# 5VPrimary.net
KiCad netlist of a schematic drawn in Altium Designer
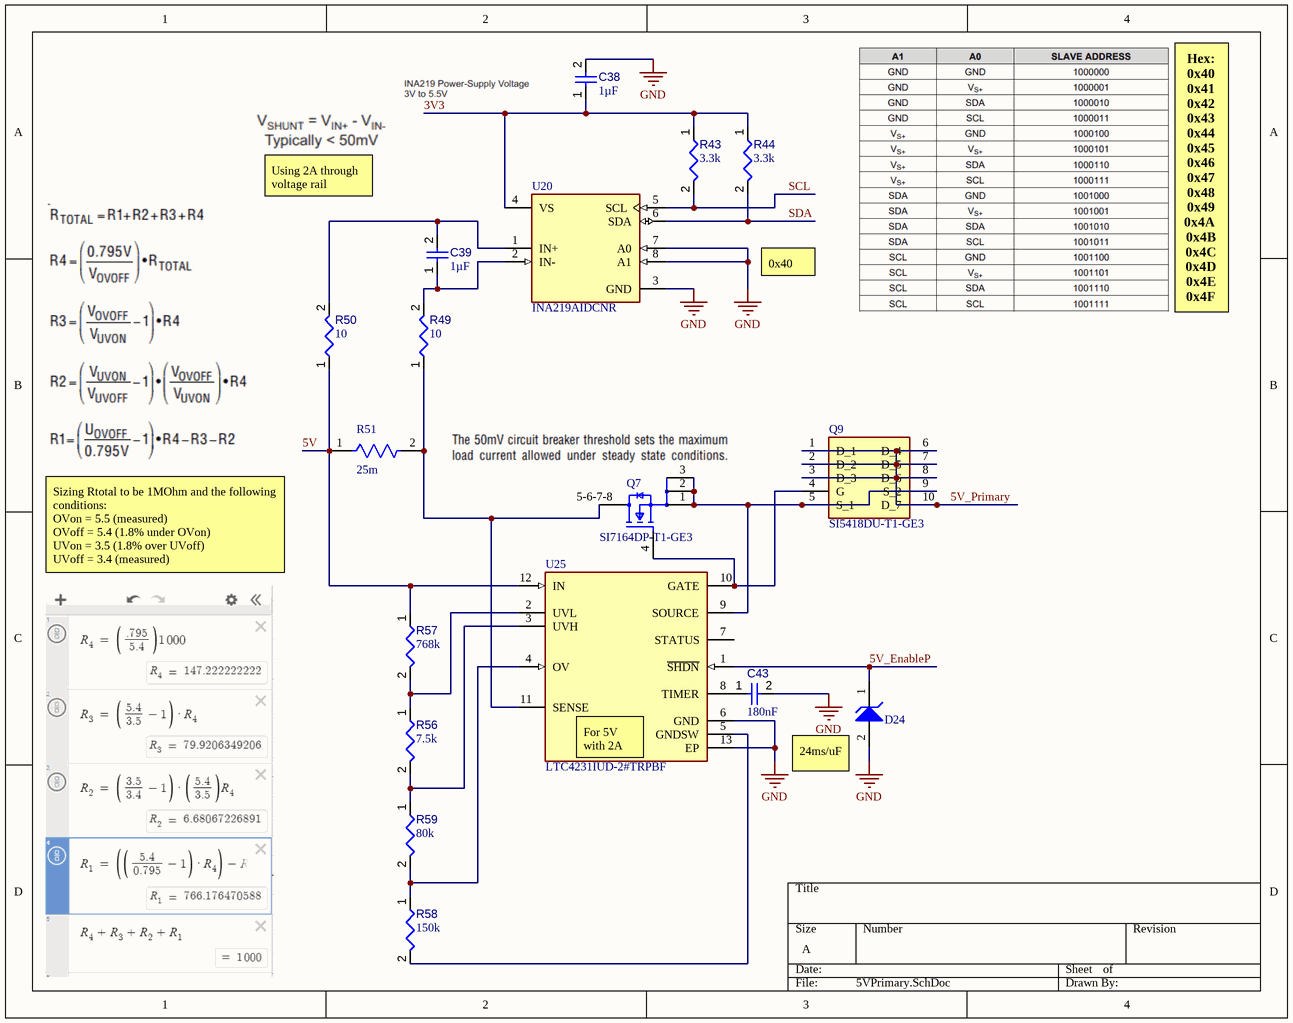
[diagram p0: 5VPrimary.SchDoc]

(export (version "E")
  (design (tool "Eeschema 10.0.6"))
  (components
    (comp (ref "C38")
      (value "1µF")
      (footprint "CAPC1608X90X35ML15T15")
      (description "Chip Capacitor, 1 uF, +/- 10%, 16 V, 0603 (1608 Metric)")
      (fields (field (name "TOLERANCE") "10%") (field (name "Comment") "Capacitor 1uF +/- 10% 16V 0603"))
      (libsource (lib "UGA SSRL Hardware Team") (part "CAP-NP-2"))
    )
    (comp (ref "C39")
      (value "1µF")
      (footprint "CAPC1608X90X40LL10T20")
      (description "Chip Capacitor, 1 uF, +/- 10%, 25 V, 0603 (1608 Metric)")
      (fields (field (name "TOLERANCE") "10%") (field (name "Comment") "Capacitor 1 uF +/- 10% 25 V 0603"))
      (libsource (lib "UGA SSRL Hardware Team") (part "CAP-NP-2"))
    )
    (comp (ref "C43")
      (value "180nF")
      (footprint "FP-C0805C-DN-IPC_A")
      (fields (field (name "Comment") "C0805C184K5RACTU"))
      (libsource (lib "UGA SSRL Hardware Team") (part "CAP-NP-2"))
    )
    (comp (ref "D24")
      (value "MM3Z3V6T1G")
      (footprint "ONSC-SOD-323-2-477-02_V")
      (description "Zener Voltage Regulator, 300 mW, 2-Pin SOD-323, Pb-Free, Tape and Reel")
      (fields (field (name "MANUFACTURER") "On Semiconductor"))
      (libsource (lib "Altium Content Vault") (part "ONSC-K1A2-2"))
    )
    (comp (ref "Q7")
      (value "SI7164DP-T1-GE3")
      (footprint "Vishay_S17-0173-SINGLE_MFG")
      (libsource (lib "UGA SSRL Hardware Team") (part "SI7164DP-T1-GE3"))
    )
    (comp (ref "Q9")
      (value "SI5418DU-T1-GE3")
      (footprint "SI5418DU-T1-GE3-Footprint-1")
      (libsource (lib "UGA SSRL Hardware Team") (part "SI5418DU-T1-GE3-Symbol-1"))
    )
    (comp (ref "R43")
      (value "3.3k")
      (footprint "FP-CRCW1210-e3-IPC_C")
      (fields
        (field (name "TOLERANCE") "5%")
        (field (name "POWER") "500mW")
        (field (name "Comment") "CRCW12103K30JNEA")
      )
      (libsource (lib "UGA SSRL Hardware Team") (part "RES-2"))
    )
    (comp (ref "R44")
      (value "3.3k")
      (footprint "FP-CRCW1210-e3-IPC_C")
      (fields
        (field (name "TOLERANCE") "5%")
        (field (name "POWER") "500mW")
        (field (name "Comment") "CRCW12103K30JNEA")
      )
      (libsource (lib "UGA SSRL Hardware Team") (part "RES-2"))
    )
    (comp (ref "R49")
      (value "10")
      (footprint "RESC0402(1005)_L")
      (description "Chip Resistor, 10 Ohms, +/-1 %, 63 mW, -55 to 155 degC, 0402")
      (fields (field (name "TOLERANCE") "1%") (field (name "POWER") "63mW"))
      (libsource (lib "UGA SSRL Hardware Team") (part "RES-2"))
    )
    (comp (ref "R50")
      (value "10")
      (footprint "RESC0402(1005)_L")
      (description "Chip Resistor, 10 Ohms, +/-1 %, 63 mW, -55 to 155 degC, 0402")
      (fields (field (name "TOLERANCE") "1%") (field (name "POWER") "63mW"))
      (libsource (lib "UGA SSRL Hardware Team") (part "RES-2"))
    )
    (comp (ref "R51")
      (value "CSR1206FK25L0")
      (footprint "FP-CSR1206-IPC_C")
      (description "General Purpose Thick Film Chip Resistor, 1206, 25mΩ, 1%, 0.5W")
      (fields (field (name "RESISTANCE") "25m") (field (name "TOLERANCE") "1%"))
      (libsource (lib "Altium Content Vault") (part "1029c3af85768c4190bb7ad29bc67b5"))
    )
    (comp (ref "R56")
      (value "7.5k")
      (footprint "FP-CRCW1206-e3-IPC_A")
      (fields
        (field (name "TOLERANCE") "1%")
        (field (name "POWER") "250mW")
        (field (name "Comment") "CRCW12067K50FKEA")
      )
      (libsource (lib "UGA SSRL Hardware Team") (part "RES-2"))
    )
    (comp (ref "R57")
      (value "768k")
      (footprint "RESC0402(1005)_L")
      (description "768K 0.063W 1% 0402 (1005 Metric)  SMD")
      (fields (field (name "TOLERANCE") "1%") (field (name "POWER") "63mW"))
      (libsource (lib "UGA SSRL Hardware Team") (part "768KR2F"))
    )
    (comp (ref "R58")
      (value "150k")
      (footprint "FP-RT1206-IPC_C")
      (description "Fixed Resistor, Thin Film, 0.25W, 150000ohm, 200V, 1% +/-Tol, 50ppm/Cel, Surface Mount, 1206")
      (fields (field (name "TOLERANCE") "1%") (field (name "POWER") "250mW"))
      (libsource (lib "UGA SSRL Hardware Team") (part "RES-2"))
    )
    (comp (ref "R59")
      (value "80k")
      (footprint "FP-PTN0603-IPC_B")
      (description "Fixed Resistor, Thin Film, 0.15W, 80000ohm, 75V, 0.1% +/-Tol, 25ppm/Cel, Surface Mount, 0603")
      (fields (field (name "POWER") "150mW") (field (name "TOLERANCE") "0.1%"))
      (libsource (lib "UGA SSRL Hardware Team") (part "RES-2"))
    )
    (comp (ref "U20")
      (value "INA219AIDCNR")
      (footprint "FP-DCN0008A-IPC_A")
      (description "Power Supply Support Circuit, Fixed, 2 Channel, 2V, PDSO8")
      (libsource (lib "UGA SSRL Hardware Team") (part "e16934b8ef90d0e345b266f0ae9cd81"))
    )
    (comp (ref "U25")
      (value "LTC4231IUD-2#TRPBF")
      (footprint "FP-UD-12-05-08-1855-IPC_A")
      (description "Switching Controller, CMOS, PQCC12")
      (libsource (lib "UGA SSRL Hardware Team") (part "94c330ae140e2337d879337fe7aaeec"))
    )
  )
  (nets
    (net (code "1") (name "/3V3") (class "Default")
      (node (ref "C38") (pin "1") (pinfunction "1_1") (pintype "passive"))
      (node (ref "R43") (pin "1") (pinfunction "1_1") (pintype "passive"))
      (node (ref "R44") (pin "1") (pinfunction "1_1") (pintype "passive"))
      (node (ref "U20") (pin "4") (pinfunction "VS_4") (pintype "power_in"))
    )
    (net (code "2") (name "/5V") (class "Default")
      (node (ref "R50") (pin "1") (pinfunction "1_1") (pintype "passive"))
      (node (ref "R51") (pin "1") (pinfunction "1_1") (pintype "passive"))
      (node (ref "R57") (pin "1") (pinfunction "1_1") (pintype "passive"))
      (node (ref "U25") (pin "12") (pinfunction "IN_12") (pintype "input"))
    )
    (net (code "3") (name "/5V_EnableP") (class "Default")
      (node (ref "D24") (pin "1") (pinfunction "K_1") (pintype "passive"))
      (node (ref "U25") (pin "1") (pinfunction "~{SHDN}_1") (pintype "input"))
    )
    (net (code "4") (name "/5V_Primary") (class "Default")
      (node (ref "Q9") (pin "1") (pinfunction "D_1_1") (pintype "passive"))
      (node (ref "Q9") (pin "10") (pinfunction "D_7_10") (pintype "passive"))
      (node (ref "Q9") (pin "2") (pinfunction "D_2_2") (pintype "passive"))
      (node (ref "Q9") (pin "3") (pinfunction "D_3_3") (pintype "passive"))
      (node (ref "Q9") (pin "6") (pinfunction "D_4_6") (pintype "passive"))
      (node (ref "Q9") (pin "7") (pinfunction "D_5_7") (pintype "passive"))
      (node (ref "Q9") (pin "8") (pinfunction "D_6_8") (pintype "passive"))
    )
    (net (code "5") (name "/SCL") (class "Default")
      (node (ref "R43") (pin "2") (pinfunction "2_2") (pintype "passive"))
      (node (ref "U20") (pin "5") (pinfunction "SCL_5") (pintype "input"))
    )
    (net (code "6") (name "/SDA") (class "Default")
      (node (ref "R44") (pin "2") (pinfunction "2_2") (pintype "passive"))
      (node (ref "U20") (pin "6") (pinfunction "SDA_6") (pintype "bidirectional"))
    )
    (net (code "7") (name "GND") (class "Default")
      (node (ref "C38") (pin "2") (pinfunction "2_2") (pintype "passive"))
      (node (ref "C43") (pin "2") (pinfunction "2_2") (pintype "passive"))
      (node (ref "D24") (pin "2") (pinfunction "A_2") (pintype "passive"))
      (node (ref "U20") (pin "3") (pinfunction "GND_3") (pintype "power_in"))
      (node (ref "U20") (pin "7") (pinfunction "A0_7") (pintype "input"))
      (node (ref "U20") (pin "8") (pinfunction "A1_8") (pintype "input"))
      (node (ref "U25") (pin "13") (pinfunction "EP_13") (pintype "power_in"))
      (node (ref "U25") (pin "6") (pinfunction "GND_6") (pintype "power_in"))
    )
    (net (code "8") (name "Net-(Q7-D)") (class "Default")
      (node (ref "Q7") (pin "5-6-7-8") (pinfunction "D_5-6-7-8") (pintype "passive"))
      (node (ref "R49") (pin "1") (pinfunction "1_1") (pintype "passive"))
      (node (ref "R51") (pin "2") (pinfunction "2_2") (pintype "passive"))
      (node (ref "U25") (pin "11") (pinfunction "SENSE_11") (pintype "passive"))
    )
    (net (code "9") (name "Net-(Q7-G)") (class "Default")
      (node (ref "Q7") (pin "4") (pinfunction "G_4") (pintype "passive"))
      (node (ref "Q9") (pin "4") (pinfunction "G_4") (pintype "passive"))
      (node (ref "U25") (pin "10") (pinfunction "GATE_10") (pintype "passive"))
    )
    (net (code "10") (name "Net-(Q9-S_1)") (class "Default")
      (node (ref "Q7") (pin "1") (pinfunction "S_1") (pintype "passive"))
      (node (ref "Q7") (pin "2") (pinfunction "S_2") (pintype "passive"))
      (node (ref "Q7") (pin "3") (pinfunction "S_3") (pintype "passive"))
      (node (ref "Q9") (pin "5") (pinfunction "S_1_5") (pintype "passive"))
      (node (ref "Q9") (pin "9") (pinfunction "S_2_9") (pintype "passive"))
      (node (ref "U25") (pin "9") (pinfunction "SOURCE_9") (pintype "passive"))
    )
    (net (code "11") (name "Net-(U20-IN+)") (class "Default")
      (node (ref "C39") (pin "2") (pinfunction "2_2") (pintype "passive"))
      (node (ref "R50") (pin "2") (pinfunction "2_2") (pintype "passive"))
      (node (ref "U20") (pin "1") (pinfunction "IN+_1") (pintype "passive"))
    )
    (net (code "12") (name "Net-(U20-IN-)") (class "Default")
      (node (ref "C39") (pin "1") (pinfunction "1_1") (pintype "passive"))
      (node (ref "R49") (pin "2") (pinfunction "2_2") (pintype "passive"))
      (node (ref "U20") (pin "2") (pinfunction "IN-_2") (pintype "input"))
    )
    (net (code "13") (name "Net-(U25-GNDSW)") (class "Default")
      (node (ref "R58") (pin "2") (pinfunction "2_2") (pintype "passive"))
      (node (ref "U25") (pin "5") (pinfunction "GNDSW_5") (pintype "power_in"))
    )
    (net (code "14") (name "Net-(U25-OV)") (class "Default")
      (node (ref "R58") (pin "1") (pinfunction "1_1") (pintype "passive"))
      (node (ref "R59") (pin "2") (pinfunction "2_2") (pintype "passive"))
      (node (ref "U25") (pin "4") (pinfunction "OV_4") (pintype "input"))
    )
    (net (code "15") (name "Net-(U25-TIMER)") (class "Default")
      (node (ref "C43") (pin "1") (pinfunction "1_1") (pintype "passive"))
      (node (ref "U25") (pin "8") (pinfunction "TIMER_8") (pintype "passive"))
    )
    (net (code "16") (name "Net-(U25-UVH)") (class "Default")
      (node (ref "R56") (pin "2") (pinfunction "2_2") (pintype "passive"))
      (node (ref "R59") (pin "1") (pinfunction "1_1") (pintype "passive"))
      (node (ref "U25") (pin "3") (pinfunction "UVH_3") (pintype "passive"))
    )
    (net (code "17") (name "Net-(U25-UVL)") (class "Default")
      (node (ref "R56") (pin "1") (pinfunction "1_1") (pintype "passive"))
      (node (ref "R57") (pin "2") (pinfunction "2_2") (pintype "passive"))
      (node (ref "U25") (pin "2") (pinfunction "UVL_2") (pintype "passive"))
    )
    (net (code "18") (name "unconnected-(U25-STATUS-Pad7)") (class "Default")
      (node (ref "U25") (pin "7") (pinfunction "STATUS_7") (pintype "passive"))
    )
  )
)
